# EC_Reader_v10.net
KiCad netlist of a schematic drawn in EAGLE
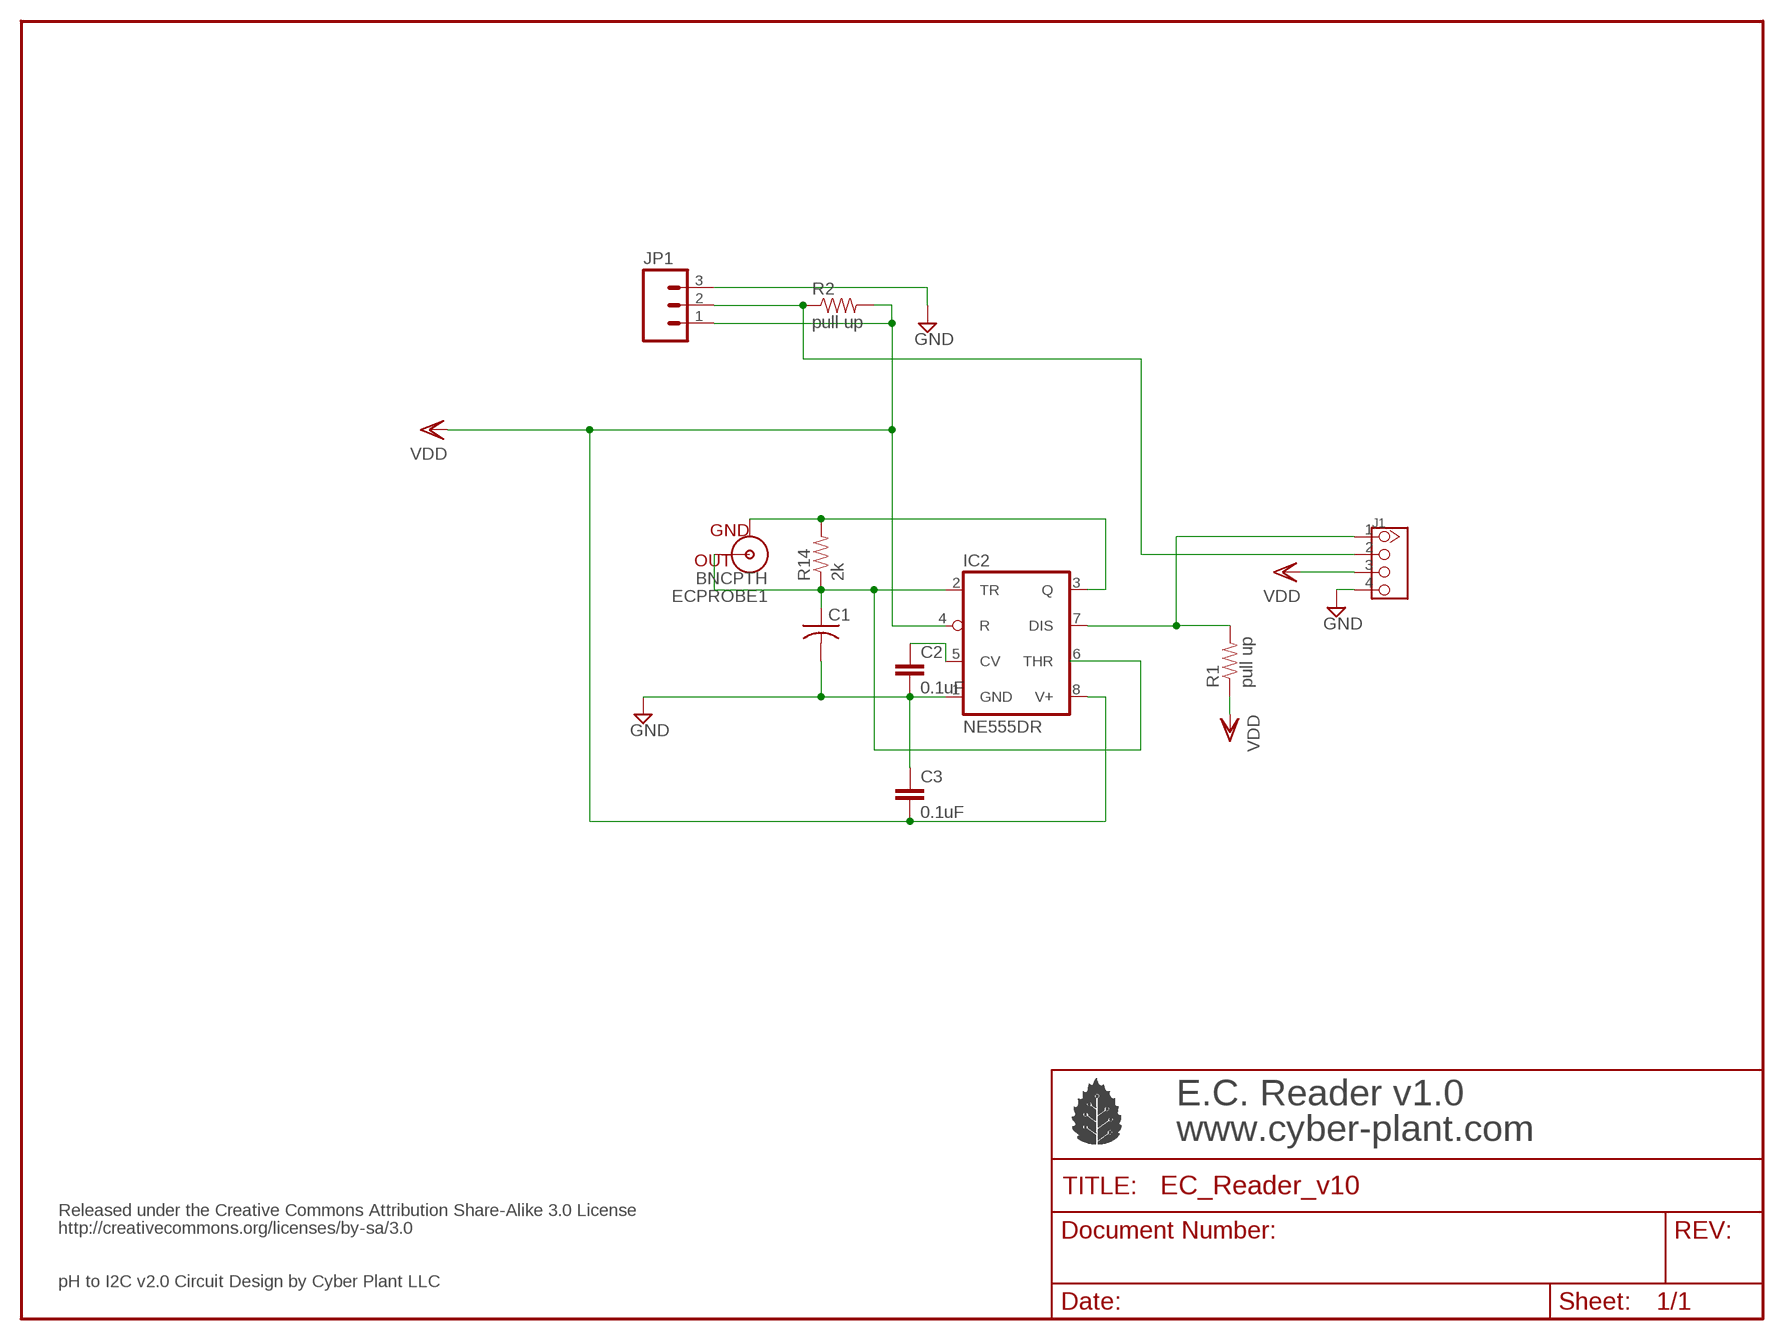
[diagram p0: schematic, sheet 1]

(export (version "E")
  (design (tool "Eeschema 10.0.6"))
  (components
    (comp (ref "C1")
      (value "C-US050-045X075")
      (footprint "eagle-import:C050-045X075")
      (libsource (lib "eagle-import") (part "C-US050-045X075"))
    )
    (comp (ref "C2")
      (value "0.1uF")
      (footprint "eagle-import:1206")
      (libsource (lib "eagle-import") (part "CAP1206"))
    )
    (comp (ref "C3")
      (value "0.1uF")
      (footprint "eagle-import:1206")
      (libsource (lib "eagle-import") (part "CAP1206"))
    )
    (comp (ref "ECPROBE1")
      (value "BNCPTH")
      (footprint "eagle-import:BNC")
      (libsource (lib "eagle-import") (part "BNCPTH"))
    )
    (comp (ref "IC2")
      (value "NE555DR")
      (footprint "eagle-import:SO08")
      (libsource (lib "eagle-import") (part "555DLM"))
    )
    (comp (ref "J1")
      (value "TWIG-4P-2.090D")
      (footprint "eagle-import:4P-2.0-90D")
      (libsource (lib "eagle-import") (part "TWIG-4P-2.090D"))
    )
    (comp (ref "JP1")
      (value "M03PTH")
      (footprint "eagle-import:1X03")
      (libsource (lib "eagle-import") (part "M03PTH"))
    )
    (comp (ref "R1")
      (value "pull up")
      (footprint "eagle-import:AXIAL-0.4")
      (libsource (lib "eagle-import") (part "RESISTORPTH-1/4W"))
    )
    (comp (ref "R2")
      (value "pull up")
      (footprint "eagle-import:AXIAL-0.4")
      (libsource (lib "eagle-import") (part "RESISTORPTH-1/4W"))
    )
    (comp (ref "R14")
      (value "2k")
      (footprint "eagle-import:1206")
      (libsource (lib "eagle-import") (part "RESISTOR1206"))
    )
  )
  (nets
    (net (code "1") (name "GND") (class "Default")
      (node (ref "C1") (pin "2") (pinfunction "2_2") (pintype "passive"))
      (node (ref "C2") (pin "2") (pinfunction "2_2") (pintype "passive"))
      (node (ref "C3") (pin "1") (pinfunction "1_1") (pintype "passive"))
      (node (ref "IC2") (pin "1") (pinfunction "GND_1") (pintype "power_in"))
      (node (ref "J1") (pin "4") (pinfunction "4_4") (pintype "bidirectional"))
      (node (ref "JP1") (pin "3") (pinfunction "3_3") (pintype "passive"))
    )
    (net (code "2") (name "Net-(ECPROBE1-OUT)") (class "Default")
      (node (ref "C1") (pin "1") (pinfunction "1_1") (pintype "passive"))
      (node (ref "ECPROBE1") (pin "S") (pinfunction "OUT_S") (pintype "bidirectional"))
      (node (ref "IC2") (pin "2") (pinfunction "TR_2") (pintype "input"))
      (node (ref "IC2") (pin "6") (pinfunction "THR_6") (pintype "input"))
      (node (ref "R14") (pin "1") (pinfunction "1_1") (pintype "passive"))
    )
    (net (code "3") (name "Net-(IC2-CV)") (class "Default")
      (node (ref "C2") (pin "1") (pinfunction "1_1") (pintype "passive"))
      (node (ref "IC2") (pin "5") (pinfunction "CV_5") (pintype "input"))
    )
    (net (code "4") (name "Net-(IC2-DIS)") (class "Default")
      (node (ref "IC2") (pin "7") (pinfunction "DIS_7") (pintype "input"))
      (node (ref "J1") (pin "1") (pinfunction "1_1") (pintype "bidirectional"))
      (node (ref "R1") (pin "P$2") (pinfunction "2_P$2") (pintype "passive"))
    )
    (net (code "5") (name "Net-(IC2-Q)") (class "Default")
      (node (ref "ECPROBE1") (pin "GND") (pinfunction "GND_GND") (pintype "bidirectional"))
      (node (ref "IC2") (pin "3") (pinfunction "Q_3") (pintype "output"))
      (node (ref "R14") (pin "2") (pinfunction "2_2") (pintype "passive"))
    )
    (net (code "6") (name "Net-(R2-1)") (class "Default")
      (node (ref "J1") (pin "2") (pinfunction "2_2") (pintype "bidirectional"))
      (node (ref "JP1") (pin "2") (pinfunction "2_2") (pintype "passive"))
      (node (ref "R2") (pin "P$1") (pinfunction "1_P$1") (pintype "passive"))
    )
    (net (code "7") (name "VDD") (class "Default")
      (node (ref "C3") (pin "2") (pinfunction "2_2") (pintype "passive"))
      (node (ref "IC2") (pin "4") (pinfunction "R_4") (pintype "input"))
      (node (ref "IC2") (pin "8") (pinfunction "V+_8") (pintype "power_in"))
      (node (ref "J1") (pin "3") (pinfunction "3_3") (pintype "bidirectional"))
      (node (ref "JP1") (pin "1") (pinfunction "1_1") (pintype "passive"))
      (node (ref "R1") (pin "P$1") (pinfunction "1_P$1") (pintype "passive"))
      (node (ref "R2") (pin "P$2") (pinfunction "2_P$2") (pintype "passive"))
    )
  )
)
